# SCH_usb-hub_2024-07-20_1.net
KiCad netlist of a schematic drawn in EasyEDA
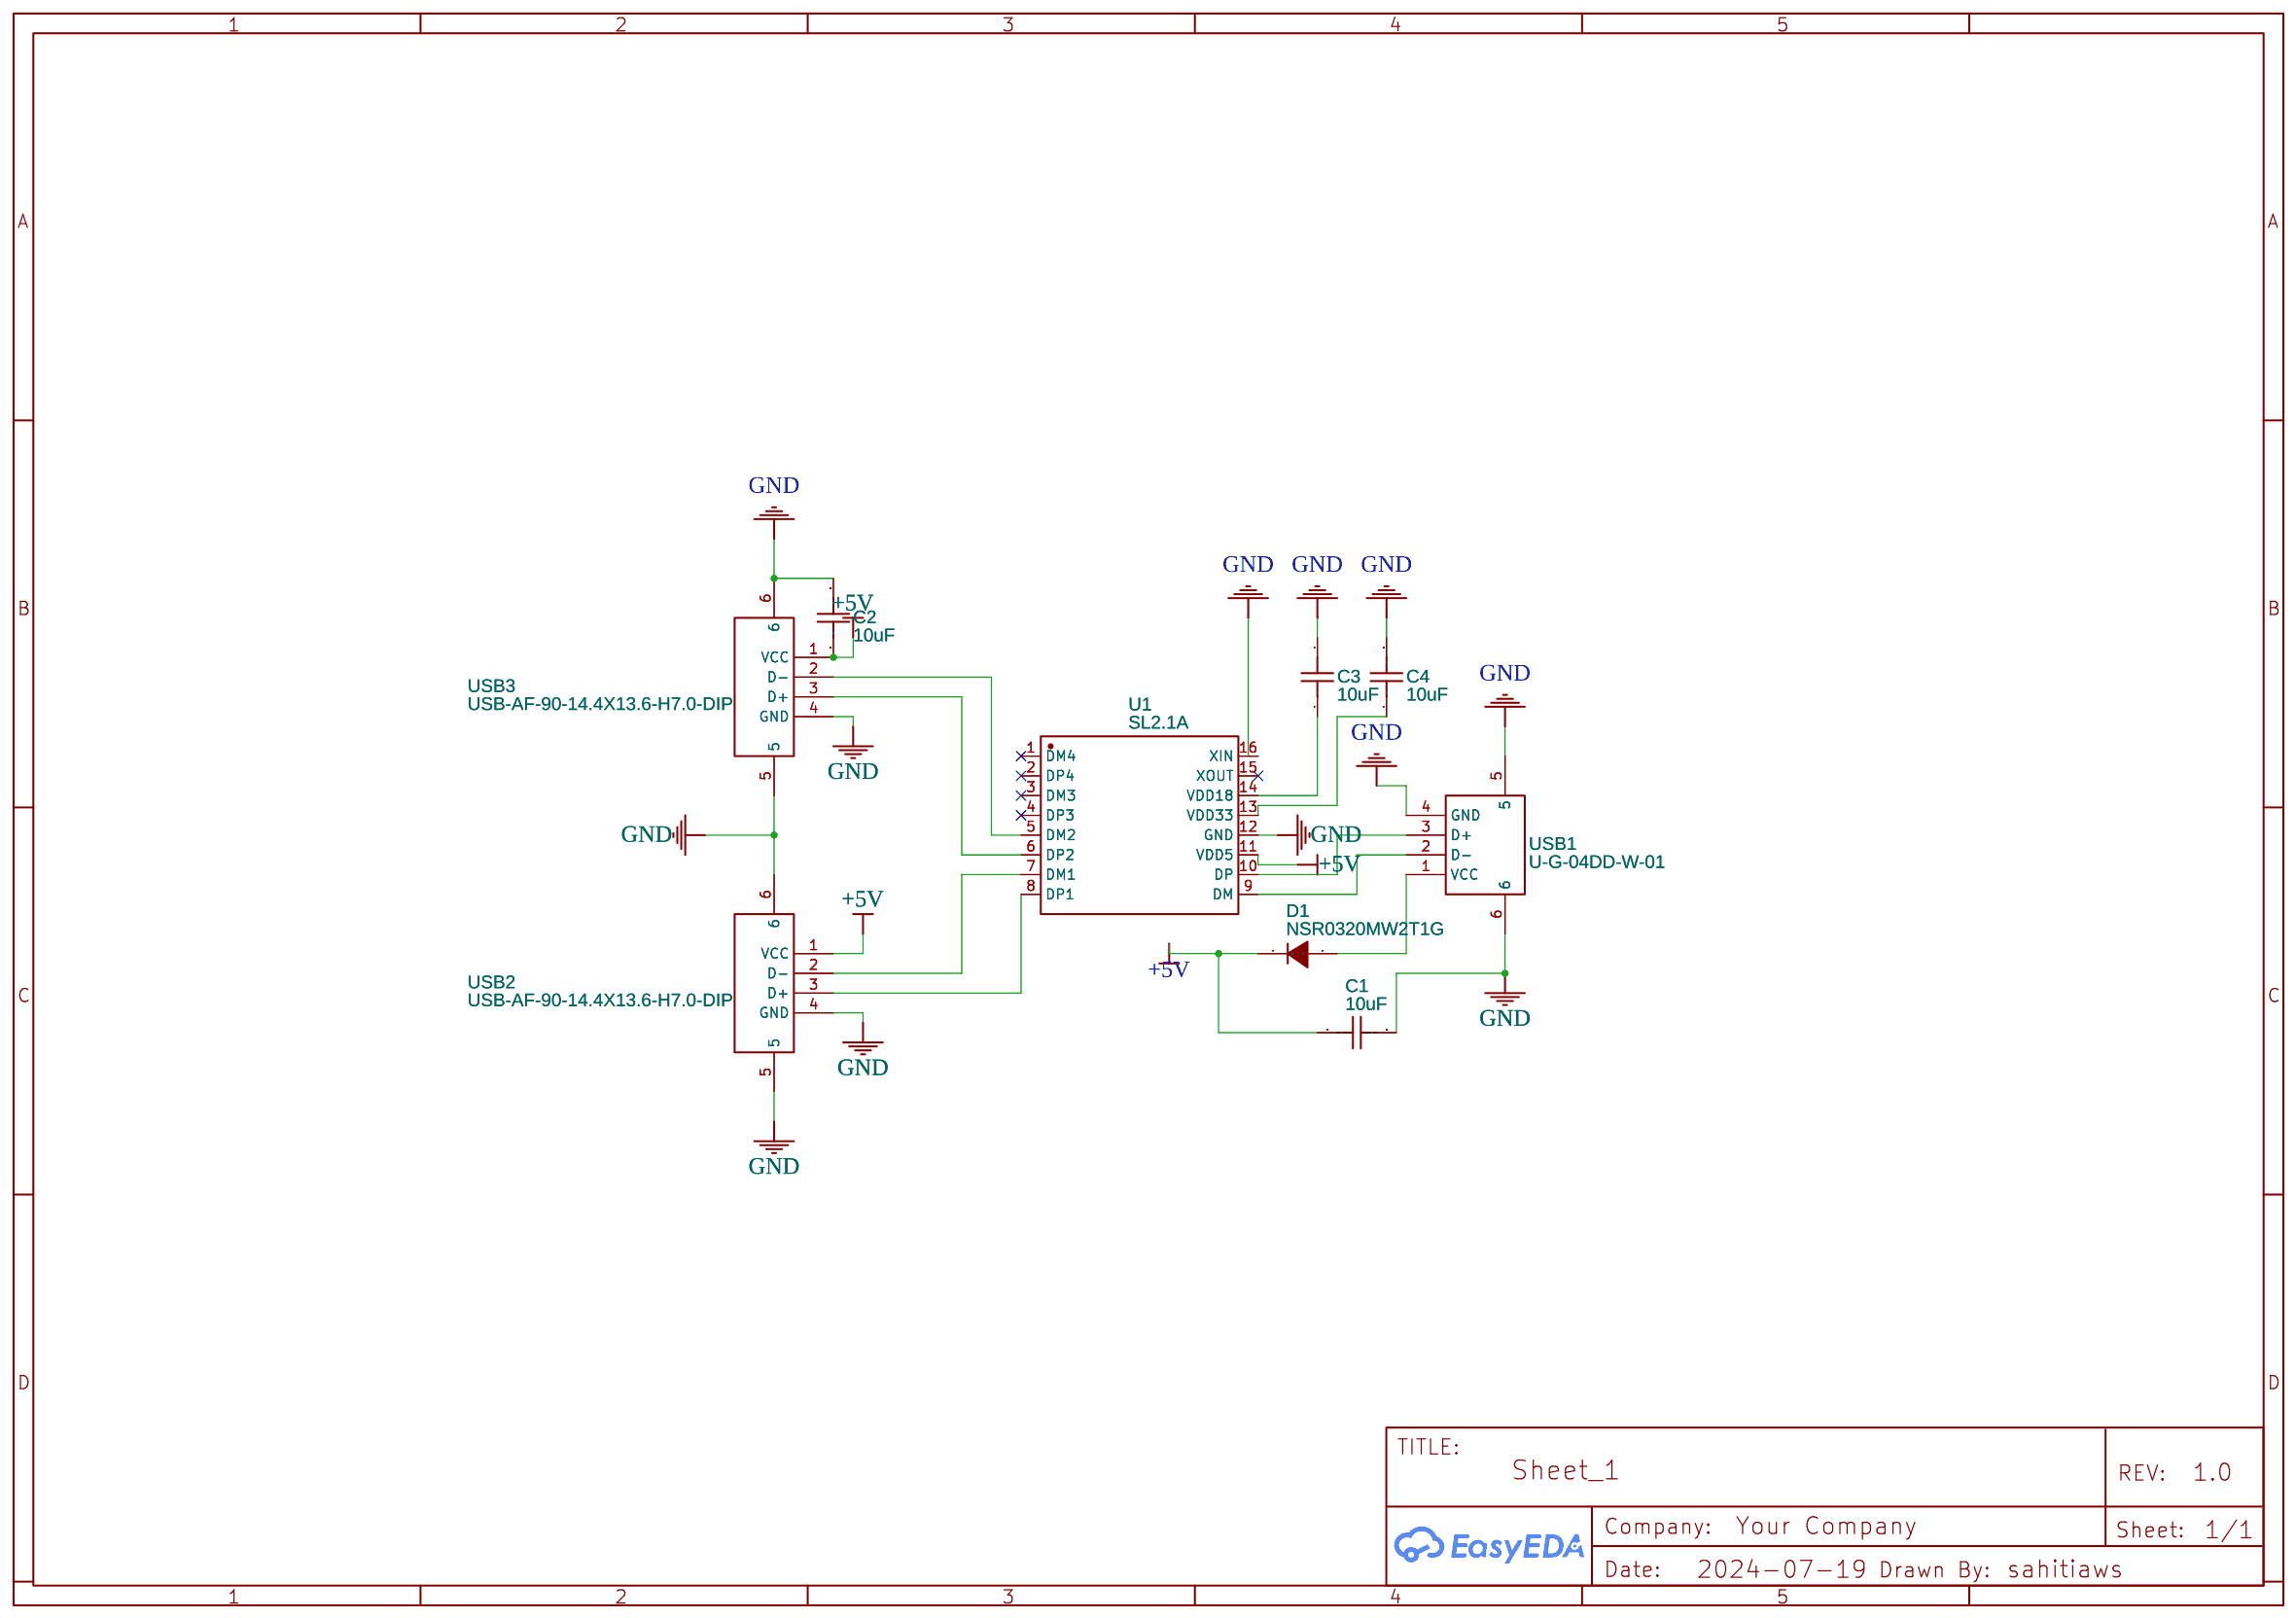
[diagram p0: schematic sheet]

(export (version "E")
  (design (tool "Eeschema 10.0.6"))
  (components
    (comp (ref "C1")
      (value "10uF")
      (fields
        (field (name "Manufacturer Part") "CL10A106KP8NNNC")
        (field (name "Manufacturer") "SAMSUNG(三星)")
      )
      (libsource (lib "") (part "CL10A106KP8NNNC_1"))
    )
    (comp (ref "C2")
      (value "10uF")
      (fields
        (field (name "Manufacturer Part") "CL10A106KP8NNNC")
        (field (name "Manufacturer") "SAMSUNG(三星)")
      )
      (libsource (lib "") (part "CL10A106KP8NNNC"))
    )
    (comp (ref "C3")
      (value "10uF")
      (fields
        (field (name "Manufacturer Part") "CL10A106KP8NNNC")
        (field (name "Manufacturer") "SAMSUNG(三星)")
      )
      (libsource (lib "") (part "CL10A106KP8NNNC"))
    )
    (comp (ref "C4")
      (value "10uF")
      (fields
        (field (name "Manufacturer Part") "CL10A106KP8NNNC")
        (field (name "Manufacturer") "SAMSUNG(三星)")
      )
      (libsource (lib "") (part "CL10A106KP8NNNC"))
    )
    (comp (ref "D1")
      (value "NSR0320MW2T1G")
      (fields (field (name "Manufacturer") "onsemi(安森美)"))
      (libsource (lib "") (part "NSR0320MW2T1G"))
    )
    (comp (ref "U1")
      (value "SL2.1A")
      (fields (field (name "Manufacturer") "CoreChips(和芯润德)"))
      (libsource (lib "") (part "SL2.1A"))
    )
    (comp (ref "USB1")
      (value "U-G-04DD-W-01")
      (fields (field (name "Manufacturer Part") "U-G-O4DD-W-1") (field (name "Manufacturer") "韩国韩荣"))
      (libsource (lib "") (part "U-G-04DD-W-01"))
    )
    (comp (ref "USB2")
      (value "USB-AF-90-14.4X13.6-H7.0-DIP")
      (fields (field (name "Manufacturer Part") "903-131A1011D10100") (field (name "Manufacturer") "精拓金"))
      (libsource (lib "") (part "USB-AF-90-14.4X13.6-H7.0-DIP"))
    )
    (comp (ref "USB3")
      (value "USB-AF-90-14.4X13.6-H7.0-DIP")
      (fields (field (name "Manufacturer Part") "903-131A1011D10100") (field (name "Manufacturer") "精拓金"))
      (libsource (lib "") (part "USB-AF-90-14.4X13.6-H7.0-DIP"))
    )
  )
  (nets
    (net (code "1") (name "+5V") (class "Default")
      (node (ref "C1") (pin "1") (pinfunction "1_1") (pintype "unspecified"))
      (node (ref "C2") (pin "1") (pinfunction "1_1") (pintype "unspecified"))
      (node (ref "D1") (pin "1") (pinfunction "C_1") (pintype "unspecified"))
      (node (ref "U1") (pin "11") (pinfunction "VDD5_11") (pintype "unspecified"))
      (node (ref "USB2") (pin "1") (pinfunction "VCC_1") (pintype "unspecified"))
      (node (ref "USB3") (pin "1") (pinfunction "VCC_1") (pintype "unspecified"))
    )
    (net (code "2") (name "GND") (class "Default")
      (node (ref "C1") (pin "2") (pinfunction "2_2") (pintype "unspecified"))
      (node (ref "C2") (pin "2") (pinfunction "2_2") (pintype "unspecified"))
      (node (ref "C3") (pin "2") (pinfunction "2_2") (pintype "unspecified"))
      (node (ref "C4") (pin "2") (pinfunction "2_2") (pintype "unspecified"))
      (node (ref "U1") (pin "12") (pinfunction "GND_12") (pintype "unspecified"))
      (node (ref "U1") (pin "16") (pinfunction "XIN_16") (pintype "unspecified"))
      (node (ref "USB1") (pin "4") (pinfunction "GND_4") (pintype "unspecified"))
      (node (ref "USB1") (pin "5") (pinfunction "5_5") (pintype "unspecified"))
      (node (ref "USB1") (pin "6") (pinfunction "6_6") (pintype "unspecified"))
      (node (ref "USB2") (pin "4") (pinfunction "GND_4") (pintype "unspecified"))
      (node (ref "USB2") (pin "5") (pinfunction "5_5") (pintype "unspecified"))
      (node (ref "USB2") (pin "6") (pinfunction "6_6") (pintype "unspecified"))
      (node (ref "USB3") (pin "4") (pinfunction "GND_4") (pintype "unspecified"))
      (node (ref "USB3") (pin "5") (pinfunction "5_5") (pintype "unspecified"))
      (node (ref "USB3") (pin "6") (pinfunction "6_6") (pintype "unspecified"))
    )
    (net (code "3") (name "Net-(D1-A)") (class "Default")
      (node (ref "D1") (pin "2") (pinfunction "A_2") (pintype "unspecified"))
      (node (ref "USB1") (pin "1") (pinfunction "VCC_1") (pintype "unspecified"))
    )
    (net (code "4") (name "Net-(U1-DM)") (class "Default")
      (node (ref "U1") (pin "9") (pinfunction "DM_9") (pintype "unspecified"))
      (node (ref "USB1") (pin "2") (pinfunction "D-_2") (pintype "unspecified"))
    )
    (net (code "5") (name "Net-(U1-DM1)") (class "Default")
      (node (ref "U1") (pin "7") (pinfunction "DM1_7") (pintype "unspecified"))
      (node (ref "USB2") (pin "2") (pinfunction "D-_2") (pintype "unspecified"))
    )
    (net (code "6") (name "Net-(U1-DM2)") (class "Default")
      (node (ref "U1") (pin "5") (pinfunction "DM2_5") (pintype "unspecified"))
      (node (ref "USB3") (pin "2") (pinfunction "D-_2") (pintype "unspecified"))
    )
    (net (code "7") (name "Net-(U1-DP)") (class "Default")
      (node (ref "U1") (pin "10") (pinfunction "DP_10") (pintype "unspecified"))
      (node (ref "USB1") (pin "3") (pinfunction "D+_3") (pintype "unspecified"))
    )
    (net (code "8") (name "Net-(U1-DP1)") (class "Default")
      (node (ref "U1") (pin "8") (pinfunction "DP1_8") (pintype "unspecified"))
      (node (ref "USB2") (pin "3") (pinfunction "D+_3") (pintype "unspecified"))
    )
    (net (code "9") (name "Net-(U1-DP2)") (class "Default")
      (node (ref "U1") (pin "6") (pinfunction "DP2_6") (pintype "unspecified"))
      (node (ref "USB3") (pin "3") (pinfunction "D+_3") (pintype "unspecified"))
    )
    (net (code "10") (name "Net-(U1-VDD18)") (class "Default")
      (node (ref "C3") (pin "1") (pinfunction "1_1") (pintype "unspecified"))
      (node (ref "U1") (pin "14") (pinfunction "VDD18_14") (pintype "unspecified"))
    )
    (net (code "11") (name "Net-(U1-VDD33)") (class "Default")
      (node (ref "C4") (pin "1") (pinfunction "1_1") (pintype "unspecified"))
      (node (ref "U1") (pin "13") (pinfunction "VDD33_13") (pintype "unspecified"))
    )
    (net (code "12") (name "unconnected-(U1-DM3-Pad3)") (class "Default")
      (node (ref "U1") (pin "3") (pinfunction "DM3_3") (pintype "unspecified+no_connect"))
    )
    (net (code "13") (name "unconnected-(U1-DM4-Pad1)") (class "Default")
      (node (ref "U1") (pin "1") (pinfunction "DM4_1") (pintype "unspecified+no_connect"))
    )
    (net (code "14") (name "unconnected-(U1-DP3-Pad4)") (class "Default")
      (node (ref "U1") (pin "4") (pinfunction "DP3_4") (pintype "unspecified+no_connect"))
    )
    (net (code "15") (name "unconnected-(U1-DP4-Pad2)") (class "Default")
      (node (ref "U1") (pin "2") (pinfunction "DP4_2") (pintype "unspecified+no_connect"))
    )
    (net (code "16") (name "unconnected-(U1-XOUT-Pad15)") (class "Default")
      (node (ref "U1") (pin "15") (pinfunction "XOUT_15") (pintype "unspecified+no_connect"))
    )
  )
)
